# Control.net
KiCad netlist of a schematic drawn in Altium Designer
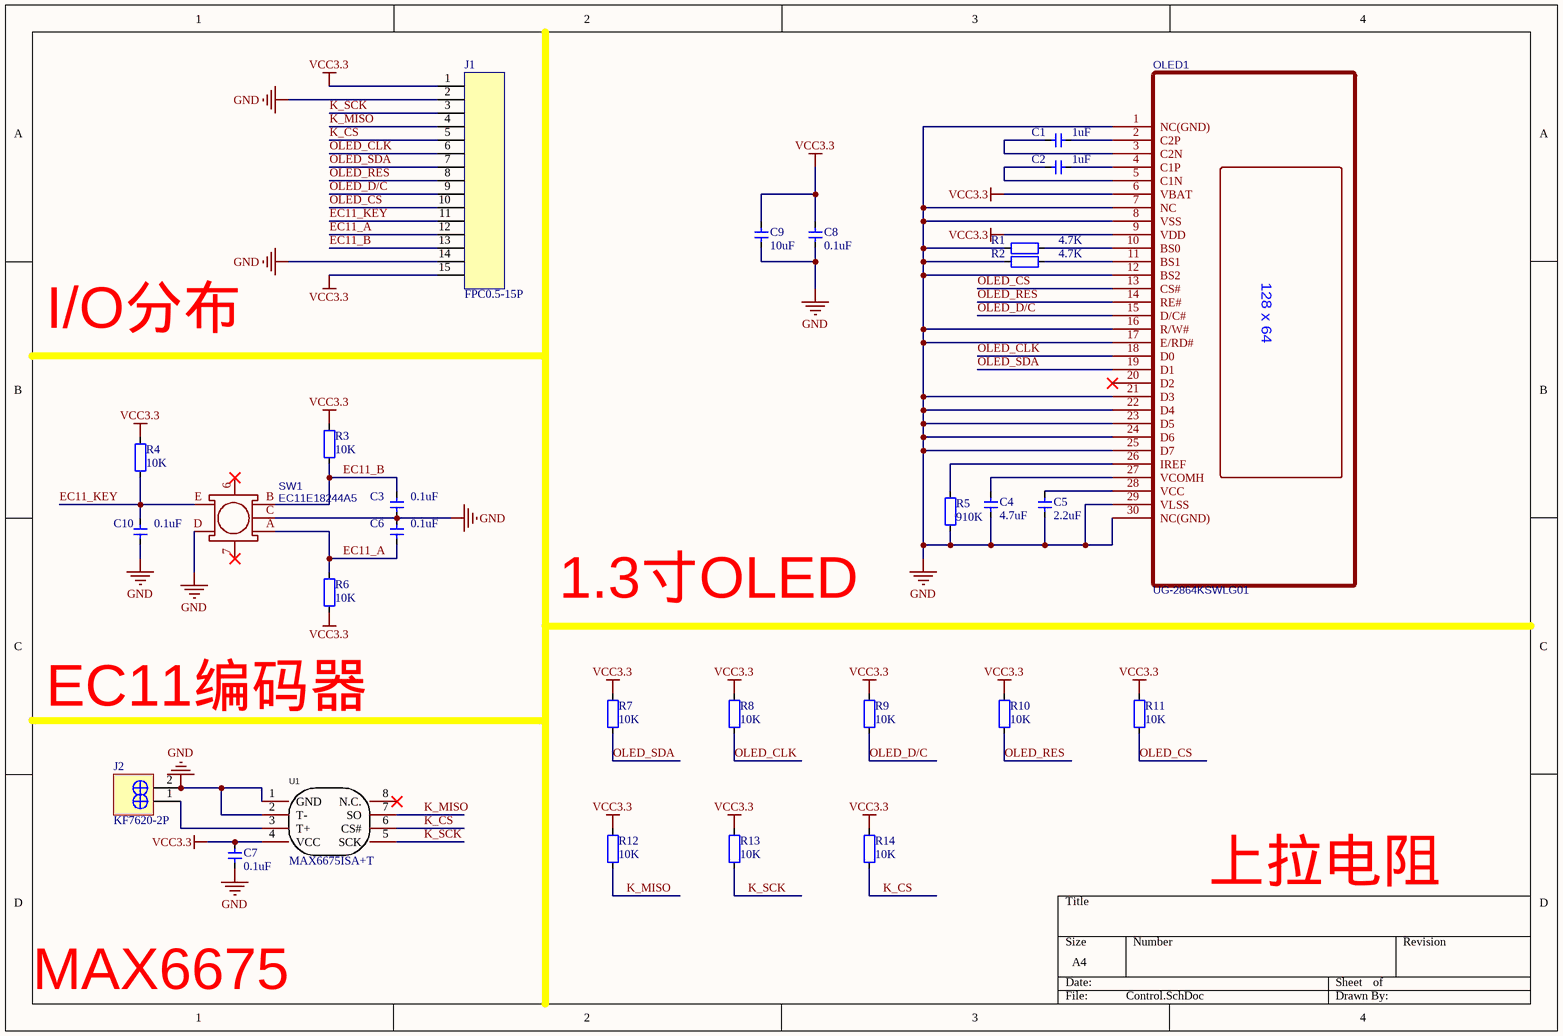
[diagram p0: Control.SchDoc]

(export (version "E")
  (design (tool "Eeschema 10.0.6"))
  (components
    (comp (ref "C1")
      (value "1uF")
      (footprint "0603C")
      (description "无极性电容")
      (libsource (lib "电容") (part "CAP"))
    )
    (comp (ref "C2")
      (value "1uF")
      (footprint "0603C")
      (description "无极性电容")
      (libsource (lib "电容") (part "CAP"))
    )
    (comp (ref "C3")
      (value "0.1uF")
      (footprint "0603C")
      (description "无极性电容")
      (libsource (lib "电容") (part "CAP"))
    )
    (comp (ref "C4")
      (value "4.7uF")
      (footprint "0603C")
      (description "无极性电容")
      (libsource (lib "电容") (part "CAP"))
    )
    (comp (ref "C5")
      (value "2.2uF")
      (footprint "0603C")
      (description "无极性电容")
      (libsource (lib "电容") (part "CAP"))
    )
    (comp (ref "C6")
      (value "0.1uF")
      (footprint "0603C")
      (description "无极性电容")
      (libsource (lib "电容") (part "CAP"))
    )
    (comp (ref "C7")
      (value "0.1uF")
      (footprint "0603C")
      (description "无极性电容")
      (libsource (lib "电容") (part "CAP"))
    )
    (comp (ref "C8")
      (value "0.1uF")
      (footprint "0603C")
      (description "无极性电容")
      (libsource (lib "电容") (part "CAP"))
    )
    (comp (ref "C9")
      (value "10uF")
      (footprint "0603C")
      (description "无极性电容")
      (libsource (lib "电容") (part "CAP"))
    )
    (comp (ref "C10")
      (value "0.1uF")
      (footprint "0603C")
      (description "无极性电容")
      (libsource (lib "电容") (part "CAP"))
    )
    (comp (ref "J1")
      (value "FPC0.5-15P")
      (footprint "FPC0.5-15P")
      (description "贴片")
      (libsource (lib "FPC") (part "FPC0.5-15P"))
    )
    (comp (ref "J2")
      (value "KF7620-2P")
      (footprint "KF7620-2P")
      (libsource (lib "KF7620") (part "KF7620-2P"))
    )
    (comp (ref "OLED1")
      (value "UG-2864KSWLG01")
      (footprint "OLED-1.3")
      (fields (field (name "BOM_SUPPLIER PART") "C113322"))
      (libsource (lib "特殊封装") (part "UG-2864KSWLG01"))
    )
    (comp (ref "R1") (value "4.7K") (footprint "0603R") (libsource (lib "") (part "RES_2")))
    (comp (ref "R2") (value "4.7K") (footprint "0603R") (libsource (lib "") (part "RES_2")))
    (comp (ref "R3") (value "10K") (footprint "0603R") (libsource (lib "电阻") (part "RES")))
    (comp (ref "R4") (value "10K") (footprint "0603R") (libsource (lib "电阻") (part "RES")))
    (comp (ref "R5") (value "910K") (footprint "0603R") (libsource (lib "电阻") (part "RES")))
    (comp (ref "R6") (value "10K") (footprint "0603R") (libsource (lib "") (part "RES_1")))
    (comp (ref "R7") (value "10K") (footprint "0603R") (libsource (lib "电阻") (part "RES")))
    (comp (ref "R8") (value "10K") (footprint "0603R") (libsource (lib "电阻") (part "RES")))
    (comp (ref "R9") (value "10K") (footprint "0603R") (libsource (lib "电阻") (part "RES")))
    (comp (ref "R10") (value "10K") (footprint "0603R") (libsource (lib "电阻") (part "RES")))
    (comp (ref "R11") (value "10K") (footprint "0603R") (libsource (lib "电阻") (part "RES")))
    (comp (ref "R12") (value "10K") (footprint "0603R") (libsource (lib "电阻") (part "RES")))
    (comp (ref "R13") (value "10K") (footprint "0603R") (libsource (lib "电阻") (part "RES")))
    (comp (ref "R14") (value "10K") (footprint "0603R") (libsource (lib "电阻") (part "RES")))
    (comp (ref "SW1")
      (value "EC11E18244A5")
      (footprint "SW-TH_EC11E18244A5")
      (fields (field (name "BOM_SUPPLIER PART") "C255515") (field (name "CONTRIBUTOR") "LCSC"))
      (libsource (lib "特殊封装") (part "EC11E18244A5"))
    )
    (comp (ref "U1")
      (value "MAX6675ISA+T")
      (footprint "SOIC-8_L5.0-W4.0-P1.27-LS6.0-BL")
      (fields (field (name "MANUFACTURER") "ADI(亚德诺)"))
      (libsource (lib "未分类IC") (part "MAX6675ISA+T"))
    )
  )
  (nets
    (net (code "1") (name "/EC11_A") (class "Default")
      (node (ref "C6") (pin "1") (pinfunction "1_1") (pintype "passive"))
      (node (ref "J1") (pin "12") (pinfunction "12_12") (pintype "passive"))
      (node (ref "R6") (pin "1") (pinfunction "1_1") (pintype "passive"))
      (node (ref "SW1") (pin "A") (pinfunction "A_A") (pintype "passive"))
    )
    (net (code "2") (name "/EC11_B") (class "Default")
      (node (ref "C3") (pin "2") (pinfunction "2_2") (pintype "passive"))
      (node (ref "J1") (pin "13") (pinfunction "13_13") (pintype "passive"))
      (node (ref "R3") (pin "1") (pinfunction "1_1") (pintype "passive"))
      (node (ref "SW1") (pin "B") (pinfunction "B_B") (pintype "passive"))
    )
    (net (code "3") (name "/EC11_KEY") (class "Default")
      (node (ref "C10") (pin "2") (pinfunction "2_2") (pintype "passive"))
      (node (ref "J1") (pin "11") (pinfunction "11_11") (pintype "passive"))
      (node (ref "R4") (pin "1") (pinfunction "1_1") (pintype "passive"))
      (node (ref "SW1") (pin "E") (pinfunction "E_E") (pintype "passive"))
    )
    (net (code "4") (name "/K_CS") (class "Default")
      (node (ref "J1") (pin "5") (pinfunction "5_5") (pintype "passive"))
      (node (ref "R14") (pin "1") (pinfunction "1_1") (pintype "passive"))
      (node (ref "U1") (pin "6") (pinfunction "CS#_6") (pintype "passive"))
    )
    (net (code "5") (name "/K_MISO") (class "Default")
      (node (ref "J1") (pin "4") (pinfunction "4_4") (pintype "passive"))
      (node (ref "R12") (pin "1") (pinfunction "1_1") (pintype "passive"))
      (node (ref "U1") (pin "7") (pinfunction "SO_7") (pintype "passive"))
    )
    (net (code "6") (name "/K_SCK") (class "Default")
      (node (ref "J1") (pin "3") (pinfunction "3_3") (pintype "passive"))
      (node (ref "R13") (pin "1") (pinfunction "1_1") (pintype "passive"))
      (node (ref "U1") (pin "5") (pinfunction "SCK_5") (pintype "passive"))
    )
    (net (code "7") (name "/OLED_CLK") (class "Default")
      (node (ref "J1") (pin "6") (pinfunction "6_6") (pintype "passive"))
      (node (ref "OLED1") (pin "18") (pinfunction "D0_18") (pintype "passive"))
      (node (ref "R8") (pin "1") (pinfunction "1_1") (pintype "passive"))
    )
    (net (code "8") (name "/OLED_CS") (class "Default")
      (node (ref "J1") (pin "10") (pinfunction "10_10") (pintype "passive"))
      (node (ref "OLED1") (pin "13") (pinfunction "CS#_13") (pintype "passive"))
      (node (ref "R11") (pin "1") (pinfunction "1_1") (pintype "passive"))
    )
    (net (code "9") (name "/OLED_D{slash}C") (class "Default")
      (node (ref "J1") (pin "9") (pinfunction "9_9") (pintype "passive"))
      (node (ref "OLED1") (pin "15") (pinfunction "D/C#_15") (pintype "passive"))
      (node (ref "R9") (pin "1") (pinfunction "1_1") (pintype "passive"))
    )
    (net (code "10") (name "/OLED_RES") (class "Default")
      (node (ref "J1") (pin "8") (pinfunction "8_8") (pintype "passive"))
      (node (ref "OLED1") (pin "14") (pinfunction "RE#_14") (pintype "passive"))
      (node (ref "R10") (pin "1") (pinfunction "1_1") (pintype "passive"))
    )
    (net (code "11") (name "/OLED_SDA") (class "Default")
      (node (ref "J1") (pin "7") (pinfunction "7_7") (pintype "passive"))
      (node (ref "OLED1") (pin "19") (pinfunction "D1_19") (pintype "passive"))
      (node (ref "R7") (pin "1") (pinfunction "1_1") (pintype "passive"))
    )
    (net (code "12") (name "GND") (class "Default")
      (node (ref "C10") (pin "1") (pinfunction "1_1") (pintype "passive"))
      (node (ref "C3") (pin "1") (pinfunction "1_1") (pintype "passive"))
      (node (ref "C4") (pin "1") (pinfunction "1_1") (pintype "passive"))
      (node (ref "C5") (pin "1") (pinfunction "1_1") (pintype "passive"))
      (node (ref "C6") (pin "2") (pinfunction "2_2") (pintype "passive"))
      (node (ref "C7") (pin "1") (pinfunction "1_1") (pintype "passive"))
      (node (ref "C8") (pin "1") (pinfunction "1_1") (pintype "passive"))
      (node (ref "C9") (pin "1") (pinfunction "1_1") (pintype "passive"))
      (node (ref "J1") (pin "14") (pinfunction "14_14") (pintype "passive"))
      (node (ref "J1") (pin "2") (pinfunction "2_2") (pintype "passive"))
      (node (ref "J2") (pin "2") (pinfunction "2_2") (pintype "passive"))
      (node (ref "OLED1") (pin "1") (pinfunction "NC(GND)_1") (pintype "passive"))
      (node (ref "OLED1") (pin "12") (pinfunction "BS2_12") (pintype "passive"))
      (node (ref "OLED1") (pin "16") (pinfunction "R/W#_16") (pintype "passive"))
      (node (ref "OLED1") (pin "17") (pinfunction "E/RD#_17") (pintype "passive"))
      (node (ref "OLED1") (pin "21") (pinfunction "D3_21") (pintype "passive"))
      (node (ref "OLED1") (pin "22") (pinfunction "D4_22") (pintype "passive"))
      (node (ref "OLED1") (pin "23") (pinfunction "D5_23") (pintype "passive"))
      (node (ref "OLED1") (pin "24") (pinfunction "D6_24") (pintype "passive"))
      (node (ref "OLED1") (pin "25") (pinfunction "D7_25") (pintype "passive"))
      (node (ref "OLED1") (pin "29") (pinfunction "VLSS_29") (pintype "passive"))
      (node (ref "OLED1") (pin "30") (pinfunction "NC(GND)_30") (pintype "passive"))
      (node (ref "OLED1") (pin "7") (pinfunction "NC_7") (pintype "passive"))
      (node (ref "OLED1") (pin "8") (pinfunction "VSS_8") (pintype "passive"))
      (node (ref "R1") (pin "1") (pinfunction "1_1") (pintype "passive"))
      (node (ref "R2") (pin "1") (pinfunction "1_1") (pintype "passive"))
      (node (ref "R5") (pin "1") (pinfunction "1_1") (pintype "passive"))
      (node (ref "SW1") (pin "C") (pinfunction "C_C") (pintype "passive"))
      (node (ref "SW1") (pin "D") (pinfunction "D_D") (pintype "passive"))
      (node (ref "U1") (pin "1") (pinfunction "GND_1") (pintype "passive"))
      (node (ref "U1") (pin "2") (pinfunction "T-_2") (pintype "passive"))
    )
    (net (code "13") (name "Net-(OLED1-BS0)") (class "Default")
      (node (ref "OLED1") (pin "10") (pinfunction "BS0_10") (pintype "passive"))
      (node (ref "R1") (pin "2") (pinfunction "2_2") (pintype "passive"))
    )
    (net (code "14") (name "Net-(OLED1-BS1)") (class "Default")
      (node (ref "OLED1") (pin "11") (pinfunction "BS1_11") (pintype "passive"))
      (node (ref "R2") (pin "2") (pinfunction "2_2") (pintype "passive"))
    )
    (net (code "15") (name "Net-(OLED1-C1N)") (class "Default")
      (node (ref "C2") (pin "1") (pinfunction "1_1") (pintype "passive"))
      (node (ref "OLED1") (pin "5") (pinfunction "C1N_5") (pintype "passive"))
    )
    (net (code "16") (name "Net-(OLED1-C1P)") (class "Default")
      (node (ref "C2") (pin "2") (pinfunction "2_2") (pintype "passive"))
      (node (ref "OLED1") (pin "4") (pinfunction "C1P_4") (pintype "passive"))
    )
    (net (code "17") (name "Net-(OLED1-C2N)") (class "Default")
      (node (ref "C1") (pin "1") (pinfunction "1_1") (pintype "passive"))
      (node (ref "OLED1") (pin "3") (pinfunction "C2N_3") (pintype "passive"))
    )
    (net (code "18") (name "Net-(OLED1-C2P)") (class "Default")
      (node (ref "C1") (pin "2") (pinfunction "2_2") (pintype "passive"))
      (node (ref "OLED1") (pin "2") (pinfunction "C2P_2") (pintype "passive"))
    )
    (net (code "19") (name "Net-(OLED1-IREF)") (class "Default")
      (node (ref "OLED1") (pin "26") (pinfunction "IREF_26") (pintype "passive"))
      (node (ref "R5") (pin "2") (pinfunction "2_2") (pintype "passive"))
    )
    (net (code "20") (name "Net-(OLED1-VCC)") (class "Default")
      (node (ref "C5") (pin "2") (pinfunction "2_2") (pintype "passive"))
      (node (ref "OLED1") (pin "28") (pinfunction "VCC_28") (pintype "passive"))
    )
    (net (code "21") (name "Net-(OLED1-VCOMH)") (class "Default")
      (node (ref "C4") (pin "2") (pinfunction "2_2") (pintype "passive"))
      (node (ref "OLED1") (pin "27") (pinfunction "VCOMH_27") (pintype "passive"))
    )
    (net (code "22") (name "Net-(U1-T+)") (class "Default")
      (node (ref "J2") (pin "1") (pinfunction "1_1") (pintype "passive"))
      (node (ref "U1") (pin "3") (pinfunction "T+_3") (pintype "passive"))
    )
    (net (code "23") (name "VCC3.3") (class "Default")
      (node (ref "C7") (pin "2") (pinfunction "2_2") (pintype "passive"))
      (node (ref "C8") (pin "2") (pinfunction "2_2") (pintype "passive"))
      (node (ref "C9") (pin "2") (pinfunction "2_2") (pintype "passive"))
      (node (ref "J1") (pin "1") (pinfunction "1_1") (pintype "passive"))
      (node (ref "J1") (pin "15") (pinfunction "15_15") (pintype "passive"))
      (node (ref "OLED1") (pin "6") (pinfunction "VBAT_6") (pintype "passive"))
      (node (ref "OLED1") (pin "9") (pinfunction "VDD_9") (pintype "passive"))
      (node (ref "R10") (pin "2") (pinfunction "2_2") (pintype "passive"))
      (node (ref "R11") (pin "2") (pinfunction "2_2") (pintype "passive"))
      (node (ref "R12") (pin "2") (pinfunction "2_2") (pintype "passive"))
      (node (ref "R13") (pin "2") (pinfunction "2_2") (pintype "passive"))
      (node (ref "R14") (pin "2") (pinfunction "2_2") (pintype "passive"))
      (node (ref "R3") (pin "2") (pinfunction "2_2") (pintype "passive"))
      (node (ref "R4") (pin "2") (pinfunction "2_2") (pintype "passive"))
      (node (ref "R6") (pin "2") (pinfunction "2_2") (pintype "passive"))
      (node (ref "R7") (pin "2") (pinfunction "2_2") (pintype "passive"))
      (node (ref "R8") (pin "2") (pinfunction "2_2") (pintype "passive"))
      (node (ref "R9") (pin "2") (pinfunction "2_2") (pintype "passive"))
      (node (ref "U1") (pin "4") (pinfunction "VCC_4") (pintype "passive"))
    )
    (net (code "24") (name "unconnected-(OLED1-D2-Pad20)") (class "Default")
      (node (ref "OLED1") (pin "20") (pinfunction "D2_20") (pintype "passive+no_connect"))
    )
    (net (code "25") (name "unconnected-(SW1-Pad6)") (class "Default")
      (node (ref "SW1") (pin "6") (pinfunction "6_6") (pintype "passive+no_connect"))
    )
    (net (code "26") (name "unconnected-(SW1-Pad7)") (class "Default")
      (node (ref "SW1") (pin "7") (pinfunction "7_7") (pintype "passive+no_connect"))
    )
    (net (code "27") (name "unconnected-(U1-N.C.-Pad8)") (class "Default")
      (node (ref "U1") (pin "8") (pinfunction "N.C._8") (pintype "passive+no_connect"))
    )
  )
)
